# 8_Clock_buffer.net
KiCad netlist of a schematic drawn in Altium Designer
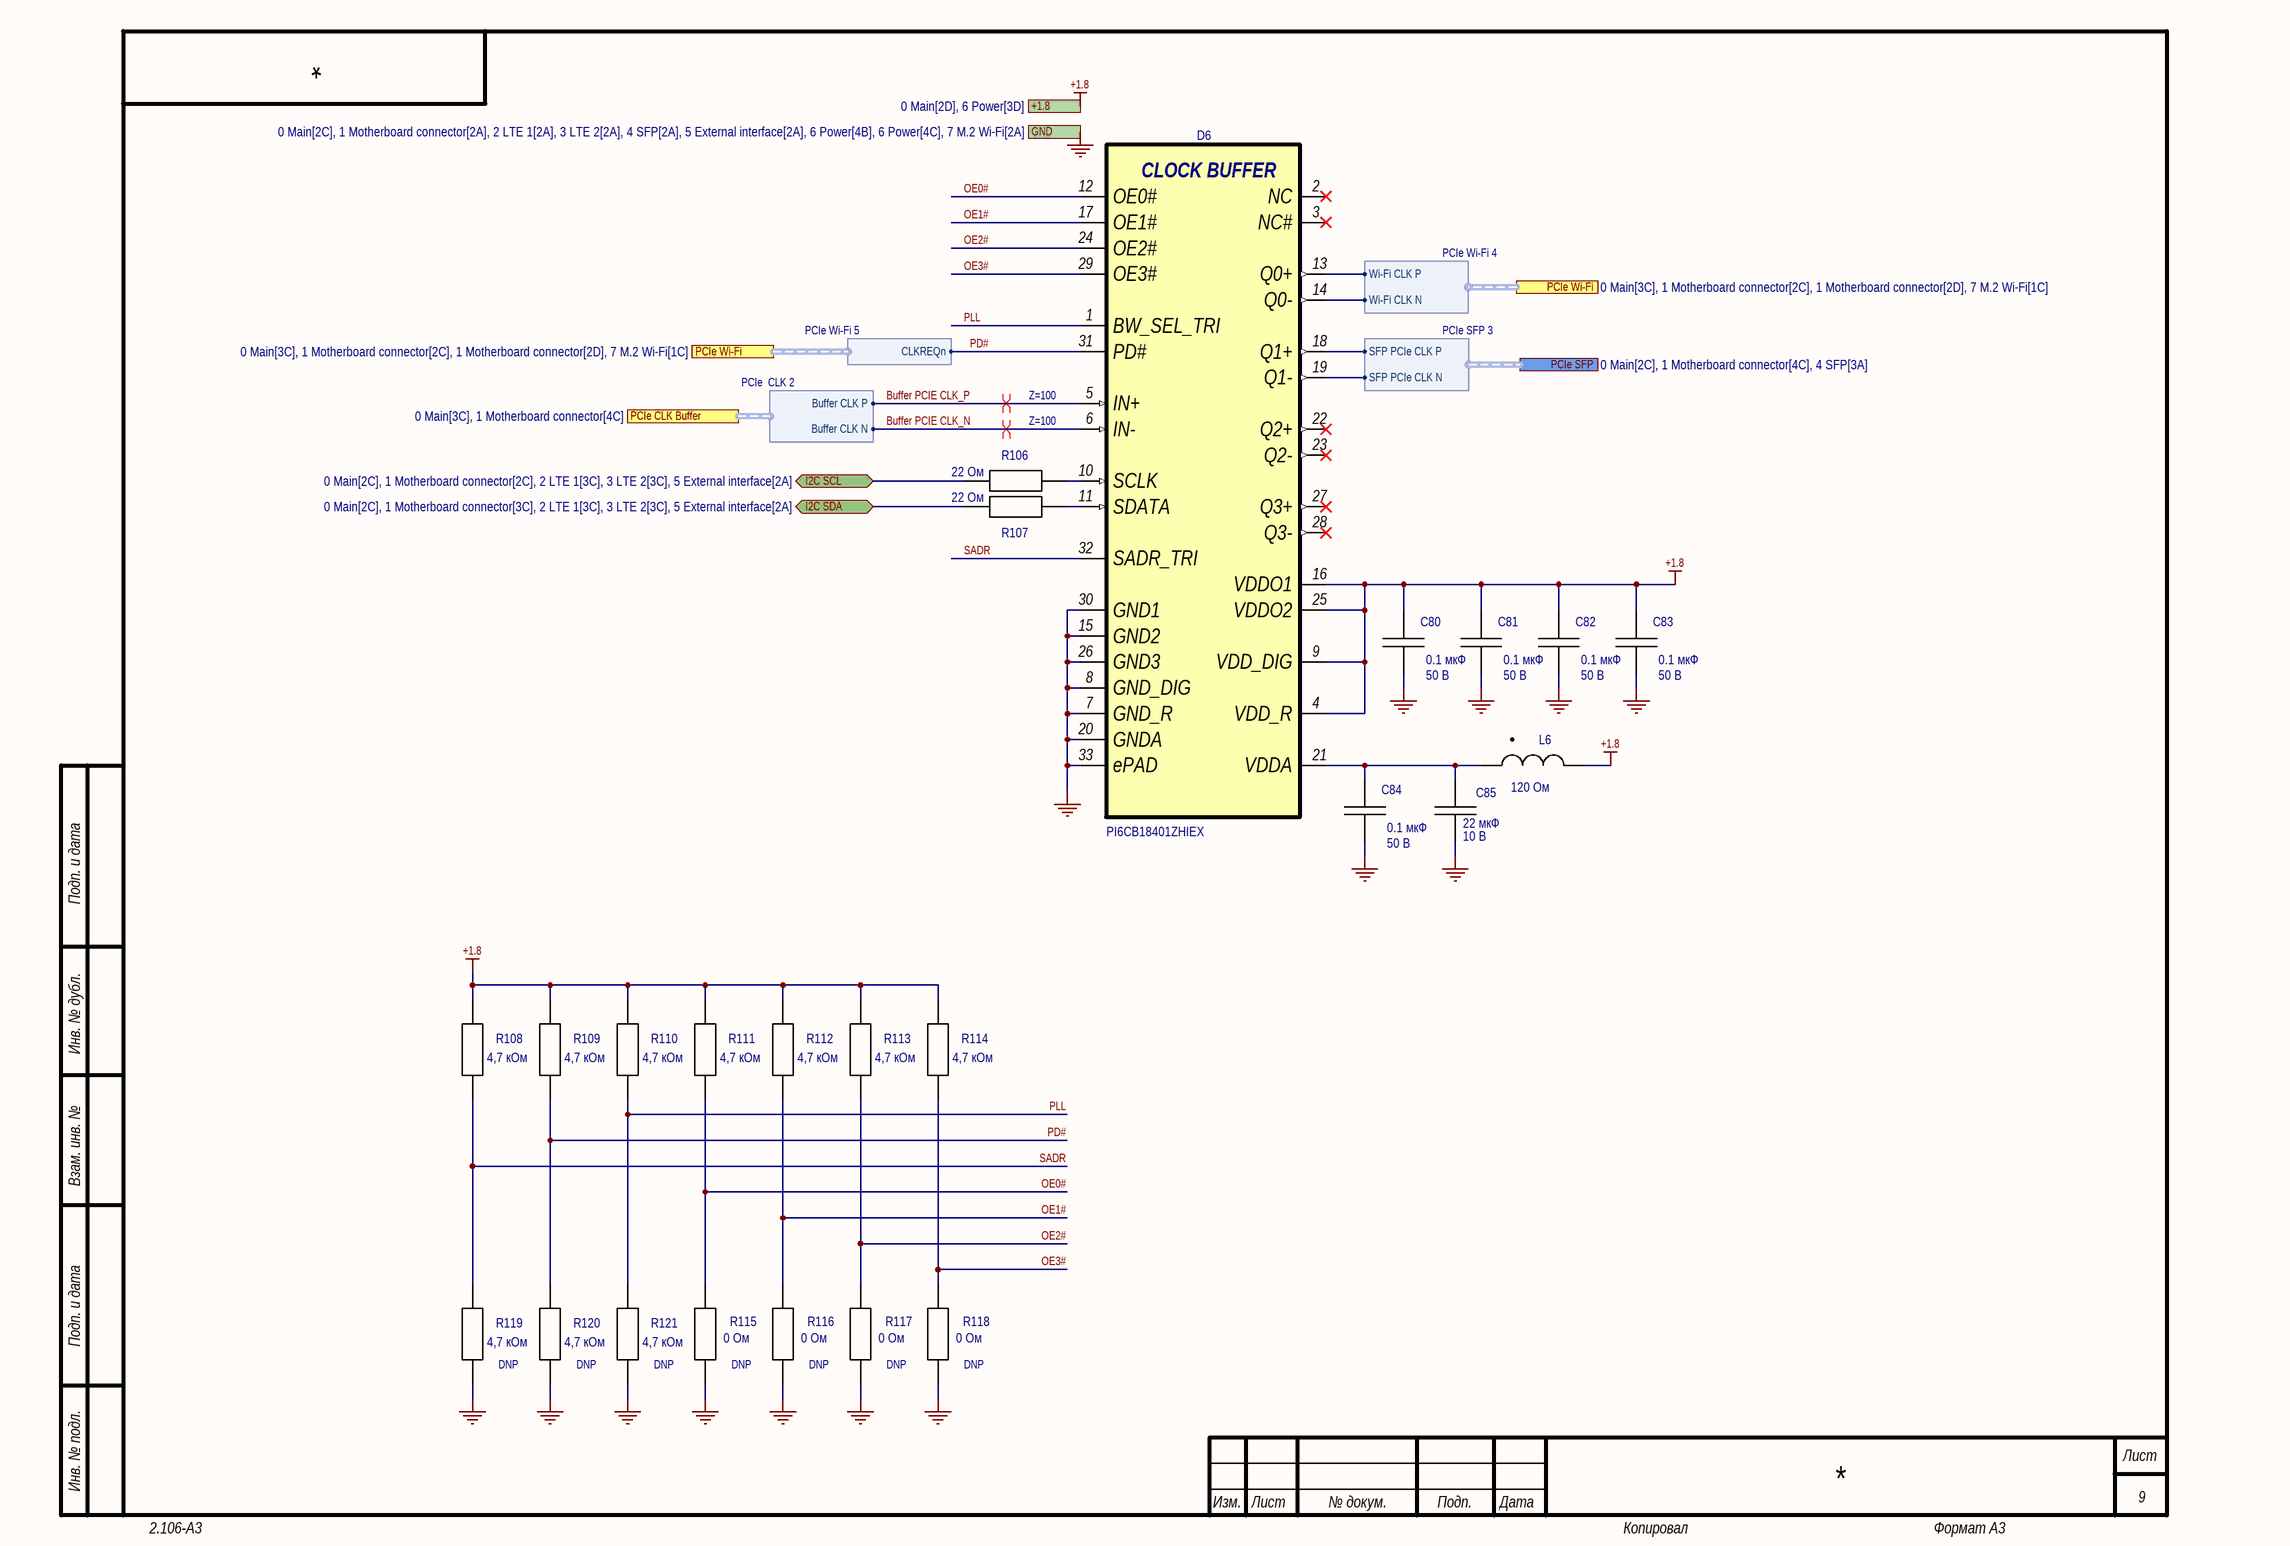
[diagram p0: 8 Clock buffer.SchDoc]

(export (version "E")
  (design (tool "Eeschema 10.0.6"))
  (components
    (comp (ref "C80")
      (value "0.1 мкФ")
      (footprint "CAP_0402")
      (description "Конденсатор CHIP-0402 0.1 мкФ 50 В 10% X7R")
      (fields
        (field (name "PARTNUMBER") "CC0402KRX7R9BB104")
        (field (name "TOLERANCE") "10%")
        (field (name "НАПРЯЖЕНИЕ") "50 В")
        (field (name "AUTOR") "Admin")
      )
      (libsource (lib "Database_Altium") (part "STD_CAP"))
    )
    (comp (ref "C81")
      (value "0.1 мкФ")
      (footprint "CAP_0402")
      (description "Конденсатор CHIP-0402 0.1 мкФ 50 В 10% X7R")
      (fields
        (field (name "PARTNUMBER") "CC0402KRX7R9BB104")
        (field (name "TOLERANCE") "10%")
        (field (name "НАПРЯЖЕНИЕ") "50 В")
        (field (name "AUTOR") "Admin")
      )
      (libsource (lib "Database_Altium") (part "STD_CAP"))
    )
    (comp (ref "C82")
      (value "0.1 мкФ")
      (footprint "CAP_0402")
      (description "Конденсатор CHIP-0402 0.1 мкФ 50 В 10% X7R")
      (fields
        (field (name "PARTNUMBER") "CC0402KRX7R9BB104")
        (field (name "TOLERANCE") "10%")
        (field (name "НАПРЯЖЕНИЕ") "50 В")
        (field (name "AUTOR") "Admin")
      )
      (libsource (lib "Database_Altium") (part "STD_CAP"))
    )
    (comp (ref "C83")
      (value "0.1 мкФ")
      (footprint "CAP_0402")
      (description "Конденсатор CHIP-0402 0.1 мкФ 50 В 10% X7R")
      (fields
        (field (name "PARTNUMBER") "CC0402KRX7R9BB104")
        (field (name "TOLERANCE") "10%")
        (field (name "НАПРЯЖЕНИЕ") "50 В")
        (field (name "AUTOR") "Admin")
      )
      (libsource (lib "Database_Altium") (part "STD_CAP"))
    )
    (comp (ref "C84")
      (value "0.1 мкФ")
      (footprint "CAP_0402")
      (description "Конденсатор CHIP-0402 0.1 мкФ 50 В 10% X7R")
      (fields
        (field (name "PARTNUMBER") "CC0402KRX7R9BB104")
        (field (name "TOLERANCE") "10%")
        (field (name "НАПРЯЖЕНИЕ") "50 В")
        (field (name "AUTOR") "Admin")
      )
      (libsource (lib "Database_Altium") (part "STD_CAP"))
    )
    (comp (ref "C85")
      (value "22 мкФ")
      (footprint "CAP_0603")
      (description "Конденсатор CHIP-0603 22 мкФ 10 В 20% X5R")
      (fields
        (field (name "PARTNUMBER") "GRM188R61A226ME15")
        (field (name "TOLERANCE") "20%")
        (field (name "НАПРЯЖЕНИЕ") "10 В")
        (field (name "AUTOR") "Admin")
      )
      (libsource (lib "Database_Altium") (part "STD_CAP"))
    )
    (comp (ref "D6")
      (value "PI6CB18401ZHIEX")
      (footprint "TQFN-32")
      (description "Микросхема Diodes  HCSL Fanout Buffer")
      (fields
        (field (name "VOLTAGE") "3,3В")
        (field (name "MANUFACTURER") "Diodes")
        (field (name "AUTOR") "Admin")
      )
      (libsource (lib "Database_Altium") (part "PI6CB18401ZHIEX"))
    )
    (comp (ref "L6")
      (value "120 Ом")
      (footprint "IND_0402")
      (description "Катушка индуктивности BEAD-0402 120 Ом 25%")
      (fields
        (field (name "PARTNUMBER") "BLM15AG121SN1D")
        (field (name "TOLERANCE") "25%")
        (field (name "AUTOR") "Admin")
      )
      (libsource (lib "Database_Altium") (part "STD_IND"))
    )
    (comp (ref "R106")
      (value "22 Ом")
      (footprint "RES_0402")
      (description "Резистор CHIP-0402 22 Ом 1%")
      (fields
        (field (name "PARTNUMBER") "RC0402FR-0722RL")
        (field (name "TOLERANCE") "1%")
        (field (name "AUTOR") "Цислав А.Н.")
      )
      (libsource (lib "Database_Altium") (part "STD_RES"))
    )
    (comp (ref "R107")
      (value "22 Ом")
      (footprint "RES_0402")
      (description "Резистор CHIP-0402 22 Ом 1%")
      (fields
        (field (name "PARTNUMBER") "RC0402FR-0722RL")
        (field (name "TOLERANCE") "1%")
        (field (name "AUTOR") "Цислав А.Н.")
      )
      (libsource (lib "Database_Altium") (part "STD_RES"))
    )
    (comp (ref "R108")
      (value "4,7 кОм")
      (footprint "RES_0402")
      (description "Резистор CHIP-0402 4,7 кОм 1%")
      (fields
        (field (name "PARTNUMBER") "RC0402FR-074K7L")
        (field (name "TOLERANCE") "1%")
        (field (name "AUTOR") "Цислав А.Н.")
      )
      (libsource (lib "Database_Altium") (part "STD_RES"))
    )
    (comp (ref "R109")
      (value "4,7 кОм")
      (footprint "RES_0402")
      (description "Резистор CHIP-0402 4,7 кОм 1%")
      (fields
        (field (name "PARTNUMBER") "RC0402FR-074K7L")
        (field (name "TOLERANCE") "1%")
        (field (name "AUTOR") "Цислав А.Н.")
      )
      (libsource (lib "Database_Altium") (part "STD_RES"))
    )
    (comp (ref "R110")
      (value "4,7 кОм")
      (footprint "RES_0402")
      (description "Резистор CHIP-0402 4,7 кОм 1%")
      (fields
        (field (name "PARTNUMBER") "RC0402FR-074K7L")
        (field (name "TOLERANCE") "1%")
        (field (name "AUTOR") "Цислав А.Н.")
      )
      (libsource (lib "Database_Altium") (part "STD_RES"))
    )
    (comp (ref "R111")
      (value "4,7 кОм")
      (footprint "RES_0402")
      (description "Резистор CHIP-0402 4,7 кОм 1%")
      (fields
        (field (name "PARTNUMBER") "RC0402FR-074K7L")
        (field (name "TOLERANCE") "1%")
        (field (name "AUTOR") "Цислав А.Н.")
      )
      (libsource (lib "Database_Altium") (part "STD_RES"))
    )
    (comp (ref "R112")
      (value "4,7 кОм")
      (footprint "RES_0402")
      (description "Резистор CHIP-0402 4,7 кОм 1%")
      (fields
        (field (name "PARTNUMBER") "RC0402FR-074K7L")
        (field (name "TOLERANCE") "1%")
        (field (name "AUTOR") "Цислав А.Н.")
      )
      (libsource (lib "Database_Altium") (part "STD_RES"))
    )
    (comp (ref "R113")
      (value "4,7 кОм")
      (footprint "RES_0402")
      (description "Резистор CHIP-0402 4,7 кОм 1%")
      (fields
        (field (name "PARTNUMBER") "RC0402FR-074K7L")
        (field (name "TOLERANCE") "1%")
        (field (name "AUTOR") "Цислав А.Н.")
      )
      (libsource (lib "Database_Altium") (part "STD_RES"))
    )
    (comp (ref "R114")
      (value "4,7 кОм")
      (footprint "RES_0402")
      (description "Резистор CHIP-0402 4,7 кОм 1%")
      (fields
        (field (name "PARTNUMBER") "RC0402FR-074K7L")
        (field (name "TOLERANCE") "1%")
        (field (name "AUTOR") "Цислав А.Н.")
      )
      (libsource (lib "Database_Altium") (part "STD_RES"))
    )
    (comp (ref "R115")
      (value "0 Ом")
      (footprint "RES_0402")
      (description "Резистор CHIP-0402 0 Ом 5%")
      (fields
        (field (name "PARTNUMBER") "RC0402JR-070RL")
        (field (name "TOLERANCE") "5%")
        (field (name "AUTOR") "Admin")
      )
      (libsource (lib "Database_Altium") (part "STD_RES"))
    )
    (comp (ref "R116")
      (value "0 Ом")
      (footprint "RES_0402")
      (description "Резистор CHIP-0402 0 Ом 5%")
      (fields
        (field (name "PARTNUMBER") "RC0402JR-070RL")
        (field (name "TOLERANCE") "5%")
        (field (name "AUTOR") "Admin")
      )
      (libsource (lib "Database_Altium") (part "STD_RES"))
    )
    (comp (ref "R117")
      (value "0 Ом")
      (footprint "RES_0402")
      (description "Резистор CHIP-0402 0 Ом 5%")
      (fields
        (field (name "PARTNUMBER") "RC0402JR-070RL")
        (field (name "TOLERANCE") "5%")
        (field (name "AUTOR") "Admin")
      )
      (libsource (lib "Database_Altium") (part "STD_RES"))
    )
    (comp (ref "R118")
      (value "0 Ом")
      (footprint "RES_0402")
      (description "Резистор CHIP-0402 0 Ом 5%")
      (fields
        (field (name "PARTNUMBER") "RC0402JR-070RL")
        (field (name "TOLERANCE") "5%")
        (field (name "AUTOR") "Admin")
      )
      (libsource (lib "Database_Altium") (part "STD_RES"))
    )
    (comp (ref "R119")
      (value "4,7 кОм")
      (footprint "RES_0402")
      (description "Резистор CHIP-0402 4,7 кОм 1%")
      (fields
        (field (name "PARTNUMBER") "RC0402FR-074K7L")
        (field (name "TOLERANCE") "1%")
        (field (name "AUTOR") "Цислав А.Н.")
      )
      (libsource (lib "Database_Altium") (part "STD_RES"))
    )
    (comp (ref "R120")
      (value "4,7 кОм")
      (footprint "RES_0402")
      (description "Резистор CHIP-0402 4,7 кОм 1%")
      (fields
        (field (name "PARTNUMBER") "RC0402FR-074K7L")
        (field (name "TOLERANCE") "1%")
        (field (name "AUTOR") "Цислав А.Н.")
      )
      (libsource (lib "Database_Altium") (part "STD_RES"))
    )
    (comp (ref "R121")
      (value "4,7 кОм")
      (footprint "RES_0402")
      (description "Резистор CHIP-0402 4,7 кОм 1%")
      (fields
        (field (name "PARTNUMBER") "RC0402FR-074K7L")
        (field (name "TOLERANCE") "1%")
        (field (name "AUTOR") "Цислав А.Н.")
      )
      (libsource (lib "Database_Altium") (part "STD_RES"))
    )
  )
  (nets
    (net (code "9") (name "+1.8") (class "Default")
      (node (ref "C80") (pin "1") (pinfunction "1_1") (pintype "passive"))
      (node (ref "C81") (pin "1") (pinfunction "1_1") (pintype "passive"))
      (node (ref "C82") (pin "1") (pinfunction "1_1") (pintype "passive"))
      (node (ref "C83") (pin "1") (pinfunction "1_1") (pintype "passive"))
      (node (ref "D6") (pin "16") (pinfunction "VDDO1_16") (pintype "power_in"))
      (node (ref "D6") (pin "25") (pinfunction "VDDO2_25") (pintype "power_in"))
      (node (ref "D6") (pin "4") (pinfunction "VDD_R_4") (pintype "power_in"))
      (node (ref "D6") (pin "9") (pinfunction "VDD_DIG_9") (pintype "power_in"))
      (node (ref "L6") (pin "2") (pinfunction "2_2") (pintype "passive"))
      (node (ref "R108") (pin "2") (pinfunction "2_2") (pintype "passive"))
      (node (ref "R109") (pin "2") (pinfunction "2_2") (pintype "passive"))
      (node (ref "R110") (pin "2") (pinfunction "2_2") (pintype "passive"))
      (node (ref "R111") (pin "2") (pinfunction "2_2") (pintype "passive"))
      (node (ref "R112") (pin "2") (pinfunction "2_2") (pintype "passive"))
      (node (ref "R113") (pin "2") (pinfunction "2_2") (pintype "passive"))
      (node (ref "R114") (pin "2") (pinfunction "2_2") (pintype "passive"))
    )
    (net (code "10") (name "/Buffer PCIE CLK_N") (class "Default")
      (node (ref "D6") (pin "6") (pinfunction "IN-_6") (pintype "input"))
    )
    (net (code "11") (name "/Buffer PCIE CLK_P") (class "Default")
      (node (ref "D6") (pin "5") (pinfunction "IN+_5") (pintype "input"))
    )
    (net (code "12") (name "/I2C SCL") (class "Default")
      (node (ref "R106") (pin "2") (pinfunction "2_2") (pintype "passive"))
    )
    (net (code "13") (name "/I2C SDA") (class "Default")
      (node (ref "R107") (pin "2") (pinfunction "2_2") (pintype "passive"))
    )
    (net (code "14") (name "/OE0#") (class "Default")
      (node (ref "D6") (pin "12") (pinfunction "OE0#_12") (pintype "passive"))
      (node (ref "R111") (pin "1") (pinfunction "1_1") (pintype "passive"))
      (node (ref "R115") (pin "2") (pinfunction "2_2") (pintype "passive"))
    )
    (net (code "15") (name "/OE1#") (class "Default")
      (node (ref "D6") (pin "17") (pinfunction "OE1#_17") (pintype "passive"))
      (node (ref "R112") (pin "1") (pinfunction "1_1") (pintype "passive"))
      (node (ref "R116") (pin "2") (pinfunction "2_2") (pintype "passive"))
    )
    (net (code "16") (name "/OE2#") (class "Default")
      (node (ref "D6") (pin "24") (pinfunction "OE2#_24") (pintype "passive"))
      (node (ref "R113") (pin "1") (pinfunction "1_1") (pintype "passive"))
      (node (ref "R117") (pin "2") (pinfunction "2_2") (pintype "passive"))
    )
    (net (code "17") (name "/OE3#") (class "Default")
      (node (ref "D6") (pin "29") (pinfunction "OE3#_29") (pintype "passive"))
      (node (ref "R114") (pin "1") (pinfunction "1_1") (pintype "passive"))
      (node (ref "R118") (pin "2") (pinfunction "2_2") (pintype "passive"))
    )
    (net (code "18") (name "/PD#") (class "Default")
      (node (ref "D6") (pin "31") (pinfunction "PD#_31") (pintype "passive"))
      (node (ref "R109") (pin "1") (pinfunction "1_1") (pintype "passive"))
      (node (ref "R120") (pin "2") (pinfunction "2_2") (pintype "passive"))
    )
    (net (code "19") (name "/PLL") (class "Default")
      (node (ref "D6") (pin "1") (pinfunction "BW_SEL_TRI_1") (pintype "passive"))
      (node (ref "R110") (pin "1") (pinfunction "1_1") (pintype "passive"))
      (node (ref "R121") (pin "2") (pinfunction "2_2") (pintype "passive"))
    )
    (net (code "20") (name "/SADR") (class "Default")
      (node (ref "D6") (pin "32") (pinfunction "SADR_TRI_32") (pintype "passive"))
      (node (ref "R108") (pin "1") (pinfunction "1_1") (pintype "passive"))
      (node (ref "R119") (pin "2") (pinfunction "2_2") (pintype "passive"))
    )
    (net (code "21") (name "/SFP PCIe CLK N") (class "Default")
      (node (ref "D6") (pin "19") (pinfunction "Q1-_19") (pintype "output"))
    )
    (net (code "22") (name "/SFP PCIe CLK P") (class "Default")
      (node (ref "D6") (pin "18") (pinfunction "Q1+_18") (pintype "output"))
    )
    (net (code "23") (name "/Wi-Fi CLK N") (class "Default")
      (node (ref "D6") (pin "14") (pinfunction "Q0-_14") (pintype "output"))
    )
    (net (code "24") (name "/Wi-Fi CLK P") (class "Default")
      (node (ref "D6") (pin "13") (pinfunction "Q0+_13") (pintype "output"))
    )
    (net (code "29") (name "GND") (class "Default")
      (node (ref "C80") (pin "2") (pinfunction "2_2") (pintype "passive"))
      (node (ref "C81") (pin "2") (pinfunction "2_2") (pintype "passive"))
      (node (ref "C82") (pin "2") (pinfunction "2_2") (pintype "passive"))
      (node (ref "C83") (pin "2") (pinfunction "2_2") (pintype "passive"))
      (node (ref "C84") (pin "2") (pinfunction "2_2") (pintype "passive"))
      (node (ref "C85") (pin "2") (pinfunction "2_2") (pintype "passive"))
      (node (ref "D6") (pin "15") (pinfunction "GND2_15") (pintype "power_in"))
      (node (ref "D6") (pin "20") (pinfunction "GNDA_20") (pintype "power_in"))
      (node (ref "D6") (pin "26") (pinfunction "GND3_26") (pintype "power_in"))
      (node (ref "D6") (pin "30") (pinfunction "GND1_30") (pintype "power_in"))
      (node (ref "D6") (pin "33") (pinfunction "ePAD_33") (pintype "power_in"))
      (node (ref "D6") (pin "7") (pinfunction "GND_R_7") (pintype "power_in"))
      (node (ref "D6") (pin "8") (pinfunction "GND_DIG_8") (pintype "power_in"))
      (node (ref "R115") (pin "1") (pinfunction "1_1") (pintype "passive"))
      (node (ref "R116") (pin "1") (pinfunction "1_1") (pintype "passive"))
      (node (ref "R117") (pin "1") (pinfunction "1_1") (pintype "passive"))
      (node (ref "R118") (pin "1") (pinfunction "1_1") (pintype "passive"))
      (node (ref "R119") (pin "1") (pinfunction "1_1") (pintype "passive"))
      (node (ref "R120") (pin "1") (pinfunction "1_1") (pintype "passive"))
      (node (ref "R121") (pin "1") (pinfunction "1_1") (pintype "passive"))
    )
    (net (code "30") (name "Net-(D6-SCLK)") (class "Default")
      (node (ref "D6") (pin "10") (pinfunction "SCLK_10") (pintype "input"))
      (node (ref "R106") (pin "1") (pinfunction "1_1") (pintype "passive"))
    )
    (net (code "31") (name "Net-(D6-SDATA)") (class "Default")
      (node (ref "D6") (pin "11") (pinfunction "SDATA_11") (pintype "input"))
      (node (ref "R107") (pin "1") (pinfunction "1_1") (pintype "passive"))
    )
    (net (code "32") (name "Net-(D6-VDDA)") (class "Default")
      (node (ref "C84") (pin "1") (pinfunction "1_1") (pintype "passive"))
      (node (ref "C85") (pin "1") (pinfunction "1_1") (pintype "passive"))
      (node (ref "D6") (pin "21") (pinfunction "VDDA_21") (pintype "power_in"))
      (node (ref "L6") (pin "1") (pinfunction "1_1") (pintype "passive"))
    )
    (net (code "33") (name "unconnected-(D6-NC#-Pad3)") (class "Default")
      (node (ref "D6") (pin "3") (pinfunction "NC#_3") (pintype "passive+no_connect"))
    )
    (net (code "34") (name "unconnected-(D6-NC-Pad2)") (class "Default")
      (node (ref "D6") (pin "2") (pinfunction "NC_2") (pintype "passive+no_connect"))
    )
    (net (code "35") (name "unconnected-(D6-Q2+-Pad22)") (class "Default")
      (node (ref "D6") (pin "22") (pinfunction "Q2+_22") (pintype "output+no_connect"))
    )
    (net (code "36") (name "unconnected-(D6-Q2--Pad23)") (class "Default")
      (node (ref "D6") (pin "23") (pinfunction "Q2-_23") (pintype "output+no_connect"))
    )
    (net (code "37") (name "unconnected-(D6-Q3+-Pad27)") (class "Default")
      (node (ref "D6") (pin "27") (pinfunction "Q3+_27") (pintype "output+no_connect"))
    )
    (net (code "38") (name "unconnected-(D6-Q3--Pad28)") (class "Default")
      (node (ref "D6") (pin "28") (pinfunction "Q3-_28") (pintype "output+no_connect"))
    )
  )
)
